# WLED_SCH.net
KiCad netlist of a schematic drawn in Altium Designer
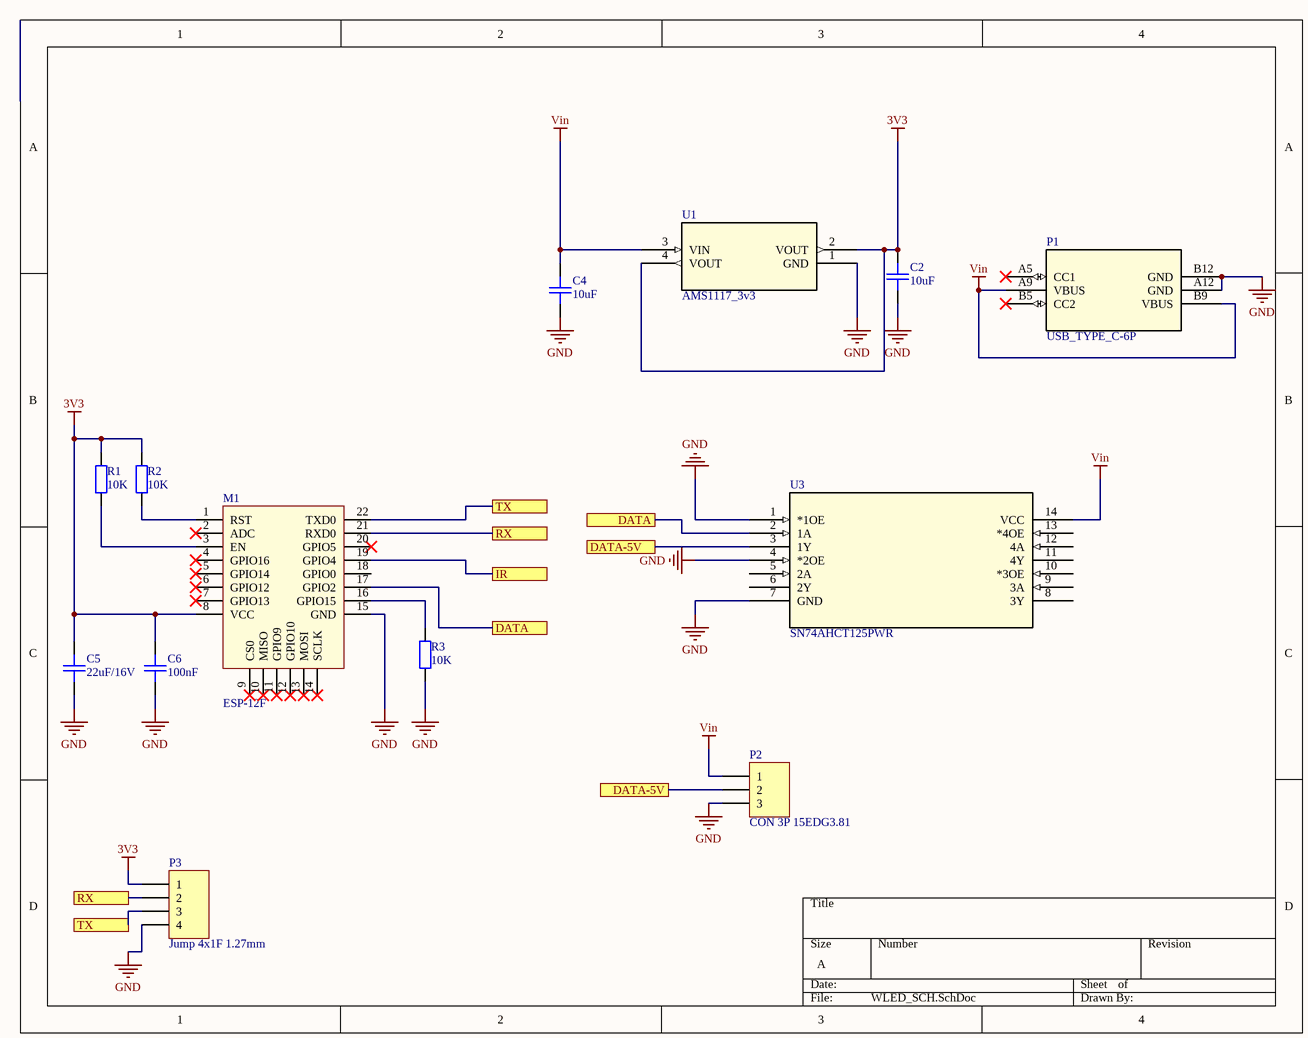
[diagram p0: WLED_SCH.SchDoc]

(export (version "E")
  (design (tool "Eeschema 10.0.6"))
  (components
    (comp (ref "C2")
      (value "10uF")
      (footprint "CAPC-0603 (1608)")
      (description "CAP CER 22UF 16V X5R 0603")
      (fields (field (name "MPN") "CL10A226MO7JZNC"))
      (libsource (lib "BYTECH_HW_LIB_2019") (part "CL10A226MO7JZNC"))
    )
    (comp (ref "C4")
      (value "10uF")
      (footprint "CAPC-0603 (1608)")
      (description "CAP CER 22UF 16V X5R 0603")
      (fields (field (name "MPN") "CL10A226MO7JZNC"))
      (libsource (lib "BYTECH_HW_LIB_2019") (part "CL10A226MO7JZNC"))
    )
    (comp (ref "C5")
      (value "22uF/16V")
      (footprint "CAPC-0603 (1608)")
      (description "CAP CER 22UF 16V X5R 0603")
      (fields (field (name "MPN") "CL10A226MO7JZNC"))
      (libsource (lib "BYTECH_HW_LIB_2019") (part "CL10A226MO7JZNC"))
    )
    (comp (ref "C6")
      (value "100nF")
      (footprint "CAPC-0603 (1608)")
      (description "CAP CER 22UF 16V X5R 0603")
      (fields (field (name "MPN") "CL10A226MO7JZNC"))
      (libsource (lib "BYTECH_HW_LIB_2019") (part "CL10A226MO7JZNC"))
    )
    (comp (ref "M1")
      (value "ESP-12F")
      (footprint "ESP-12E&F Module")
      (description "ESP-12F Module")
      (fields (field (name "MFR") "Espressif"))
      (libsource (lib "BYTECH_HW_LIB_2019") (part "ESP-12F"))
    )
    (comp (ref "P1")
      (value "USB_TYPE_C-6P")
      (footprint "USB_TYPE_C_6P")
      (libsource (lib "BYTECH_HW_LIB_2019") (part "USB_TYPE_C-6P"))
    )
    (comp (ref "P2")
      (value "CON 3P 15EDG3.81")
      (footprint "HDR_3.81MM_RA_3x1")
      (description "Header 3, pitch 3.81mm, right angle")
      (libsource (lib "BYTECH_HW_LIB_2019") (part "CON 3P 15EDG3.81"))
    )
    (comp (ref "P3")
      (value "Jump 4x1F 1.27mm")
      (footprint "JP4_1.27MM")
      (libsource (lib "BYTECH_HW_LIB_2019") (part "Jump 4x1F 1.27mm"))
    )
    (comp (ref "R1")
      (value "10K")
      (footprint "RESC-0603 (1608)")
      (description "RES SMD 10K OHM 1% 1/10W 0603")
      (fields (field (name "MPN") "RC0603FR-0710KL"))
      (libsource (lib "BYTECH_HW_LIB_2019") (part "RC0603FR-0710KL"))
    )
    (comp (ref "R2")
      (value "10K")
      (footprint "RESC-0603 (1608)")
      (description "RES SMD 10K OHM 1% 1/10W 0603")
      (fields (field (name "MPN") "RC0603FR-0710KL"))
      (libsource (lib "BYTECH_HW_LIB_2019") (part "RC0603FR-0710KL"))
    )
    (comp (ref "R3")
      (value "10K")
      (footprint "RESC-0603 (1608)")
      (description "RES SMD 10K OHM 1% 1/10W 0603")
      (fields (field (name "MPN") "RC0603FR-0710KL"))
      (libsource (lib "BYTECH_HW_LIB_2019") (part "RC0603FR-0710KL"))
    )
    (comp (ref "U1")
      (value "AMS1117_3v3")
      (footprint "SOT-223-3L_UMW")
      (libsource (lib "BYTECH_HW_LIB_2019") (part "AMS1117_3v3"))
    )
    (comp (ref "U3")
      (value "SN74AHCT125PWR")
      (footprint "PW14-L")
      (description "No Description Available")
      (fields (field (name "COPYRIGHT") "Copyright (C) 2023 Ultra Librarian. All rights reserved."))
      (libsource (lib "BYTECH_HW_LIB_2019") (part "SN74AHCT125PWR"))
    )
  )
  (nets
    (net (code "1") (name "/DATA") (class "Default")
      (node (ref "M1") (pin "17") (pinfunction "GPIO2_17") (pintype "passive"))
      (node (ref "U3") (pin "2") (pinfunction "1A_2") (pintype "input"))
    )
    (net (code "2") (name "/DATA-5V") (class "Default")
      (node (ref "P2") (pin "2") (pinfunction "2_2") (pintype "passive"))
      (node (ref "U3") (pin "3") (pinfunction "1Y_3") (pintype "passive"))
    )
    (net (code "3") (name "/IR") (class "Default")
      (node (ref "M1") (pin "19") (pinfunction "GPIO4_19") (pintype "passive"))
    )
    (net (code "4") (name "/RX") (class "Default")
      (node (ref "M1") (pin "21") (pinfunction "RXD0_21") (pintype "passive"))
      (node (ref "P3") (pin "2") (pinfunction "2_2") (pintype "passive"))
    )
    (net (code "5") (name "/TX") (class "Default")
      (node (ref "M1") (pin "22") (pinfunction "TXD0_22") (pintype "passive"))
      (node (ref "P3") (pin "3") (pinfunction "3_3") (pintype "passive"))
    )
    (net (code "6") (name "3V3") (class "Default")
      (node (ref "C2") (pin "2") (pinfunction "2_2") (pintype "passive"))
      (node (ref "C5") (pin "2") (pinfunction "2_2") (pintype "passive"))
      (node (ref "C6") (pin "2") (pinfunction "2_2") (pintype "passive"))
      (node (ref "M1") (pin "8") (pinfunction "VCC_8") (pintype "passive"))
      (node (ref "P3") (pin "1") (pinfunction "1_1") (pintype "passive"))
      (node (ref "R1") (pin "2") (pinfunction "2_2") (pintype "passive"))
      (node (ref "R2") (pin "2") (pinfunction "2_2") (pintype "passive"))
      (node (ref "U1") (pin "2") (pinfunction "VOUT_2") (pintype "output"))
      (node (ref "U1") (pin "4") (pinfunction "VOUT_4") (pintype "output"))
    )
    (net (code "7") (name "GND") (class "Default")
      (node (ref "C2") (pin "1") (pinfunction "1_1") (pintype "passive"))
      (node (ref "C4") (pin "1") (pinfunction "1_1") (pintype "passive"))
      (node (ref "C5") (pin "1") (pinfunction "1_1") (pintype "passive"))
      (node (ref "C6") (pin "1") (pinfunction "1_1") (pintype "passive"))
      (node (ref "M1") (pin "15") (pinfunction "GND_15") (pintype "passive"))
      (node (ref "P1") (pin "A12") (pinfunction "GND_A12") (pintype "power_in"))
      (node (ref "P1") (pin "B12") (pinfunction "GND_B12") (pintype "power_in"))
      (node (ref "P2") (pin "3") (pinfunction "3_3") (pintype "passive"))
      (node (ref "P3") (pin "4") (pinfunction "4_4") (pintype "passive"))
      (node (ref "R3") (pin "1") (pinfunction "1_1") (pintype "passive"))
      (node (ref "U1") (pin "1") (pinfunction "GND_1") (pintype "power_in"))
      (node (ref "U3") (pin "1") (pinfunction "*1OE_1") (pintype "input"))
      (node (ref "U3") (pin "4") (pinfunction "*2OE_4") (pintype "input"))
      (node (ref "U3") (pin "7") (pinfunction "GND_7") (pintype "power_in"))
    )
    (net (code "8") (name "Net-(M1-EN)") (class "Default")
      (node (ref "M1") (pin "3") (pinfunction "EN_3") (pintype "passive"))
      (node (ref "R1") (pin "1") (pinfunction "1_1") (pintype "passive"))
    )
    (net (code "9") (name "Net-(M1-GPIO15)") (class "Default")
      (node (ref "M1") (pin "16") (pinfunction "GPIO15_16") (pintype "passive"))
      (node (ref "R3") (pin "2") (pinfunction "2_2") (pintype "passive"))
    )
    (net (code "10") (name "Net-(M1-RST)") (class "Default")
      (node (ref "M1") (pin "1") (pinfunction "RST_1") (pintype "passive"))
      (node (ref "R2") (pin "1") (pinfunction "1_1") (pintype "passive"))
    )
    (net (code "11") (name "Vin") (class "Default")
      (node (ref "C4") (pin "2") (pinfunction "2_2") (pintype "passive"))
      (node (ref "P1") (pin "A9") (pinfunction "VBUS_A9") (pintype "power_in"))
      (node (ref "P1") (pin "B9") (pinfunction "VBUS_B9") (pintype "power_in"))
      (node (ref "P2") (pin "1") (pinfunction "1_1") (pintype "passive"))
      (node (ref "U1") (pin "3") (pinfunction "VIN_3") (pintype "input"))
      (node (ref "U3") (pin "14") (pinfunction "VCC_14") (pintype "power_in"))
    )
    (net (code "12") (name "unconnected-(M1-ADC-Pad2)") (class "Default")
      (node (ref "M1") (pin "2") (pinfunction "ADC_2") (pintype "passive+no_connect"))
    )
    (net (code "13") (name "unconnected-(M1-CS0-Pad9)") (class "Default")
      (node (ref "M1") (pin "9") (pinfunction "CS0_9") (pintype "passive+no_connect"))
    )
    (net (code "14") (name "unconnected-(M1-GPIO0-Pad18)") (class "Default")
      (node (ref "M1") (pin "18") (pinfunction "GPIO0_18") (pintype "passive"))
    )
    (net (code "15") (name "unconnected-(M1-GPIO5-Pad20)") (class "Default")
      (node (ref "M1") (pin "20") (pinfunction "GPIO5_20") (pintype "passive+no_connect"))
    )
    (net (code "16") (name "unconnected-(M1-GPIO9-Pad11)") (class "Default")
      (node (ref "M1") (pin "11") (pinfunction "GPIO9_11") (pintype "passive+no_connect"))
    )
    (net (code "17") (name "unconnected-(M1-GPIO10-Pad12)") (class "Default")
      (node (ref "M1") (pin "12") (pinfunction "GPIO10_12") (pintype "passive+no_connect"))
    )
    (net (code "18") (name "unconnected-(M1-GPIO12-Pad6)") (class "Default")
      (node (ref "M1") (pin "6") (pinfunction "GPIO12_6") (pintype "passive+no_connect"))
    )
    (net (code "19") (name "unconnected-(M1-GPIO13-Pad7)") (class "Default")
      (node (ref "M1") (pin "7") (pinfunction "GPIO13_7") (pintype "passive+no_connect"))
    )
    (net (code "20") (name "unconnected-(M1-GPIO14-Pad5)") (class "Default")
      (node (ref "M1") (pin "5") (pinfunction "GPIO14_5") (pintype "passive+no_connect"))
    )
    (net (code "21") (name "unconnected-(M1-GPIO16-Pad4)") (class "Default")
      (node (ref "M1") (pin "4") (pinfunction "GPIO16_4") (pintype "passive+no_connect"))
    )
    (net (code "22") (name "unconnected-(M1-MISO-Pad10)") (class "Default")
      (node (ref "M1") (pin "10") (pinfunction "MISO_10") (pintype "passive+no_connect"))
    )
    (net (code "23") (name "unconnected-(M1-MOSI-Pad13)") (class "Default")
      (node (ref "M1") (pin "13") (pinfunction "MOSI_13") (pintype "passive+no_connect"))
    )
    (net (code "24") (name "unconnected-(M1-SCLK-Pad14)") (class "Default")
      (node (ref "M1") (pin "14") (pinfunction "SCLK_14") (pintype "passive+no_connect"))
    )
    (net (code "25") (name "unconnected-(P1-CC1-PadA5)") (class "Default")
      (node (ref "P1") (pin "A5") (pinfunction "CC1_A5") (pintype "bidirectional+no_connect"))
    )
    (net (code "26") (name "unconnected-(P1-CC2-PadB5)") (class "Default")
      (node (ref "P1") (pin "B5") (pinfunction "CC2_B5") (pintype "bidirectional+no_connect"))
    )
    (net (code "27") (name "unconnected-(U3-*3OE-Pad10)") (class "Default")
      (node (ref "U3") (pin "10") (pinfunction "*3OE_10") (pintype "input"))
    )
    (net (code "28") (name "unconnected-(U3-*4OE-Pad13)") (class "Default")
      (node (ref "U3") (pin "13") (pinfunction "*4OE_13") (pintype "input"))
    )
    (net (code "29") (name "unconnected-(U3-2A-Pad5)") (class "Default")
      (node (ref "U3") (pin "5") (pinfunction "2A_5") (pintype "input"))
    )
    (net (code "30") (name "unconnected-(U3-2Y-Pad6)") (class "Default")
      (node (ref "U3") (pin "6") (pinfunction "2Y_6") (pintype "passive"))
    )
    (net (code "31") (name "unconnected-(U3-3A-Pad9)") (class "Default")
      (node (ref "U3") (pin "9") (pinfunction "3A_9") (pintype "input"))
    )
    (net (code "32") (name "unconnected-(U3-3Y-Pad8)") (class "Default")
      (node (ref "U3") (pin "8") (pinfunction "3Y_8") (pintype "passive"))
    )
    (net (code "33") (name "unconnected-(U3-4A-Pad12)") (class "Default")
      (node (ref "U3") (pin "12") (pinfunction "4A_12") (pintype "input"))
    )
    (net (code "34") (name "unconnected-(U3-4Y-Pad11)") (class "Default")
      (node (ref "U3") (pin "11") (pinfunction "4Y_11") (pintype "passive"))
    )
  )
)
